# I2CRJ45X8-old.net
KiCad netlist of a schematic drawn in EAGLE
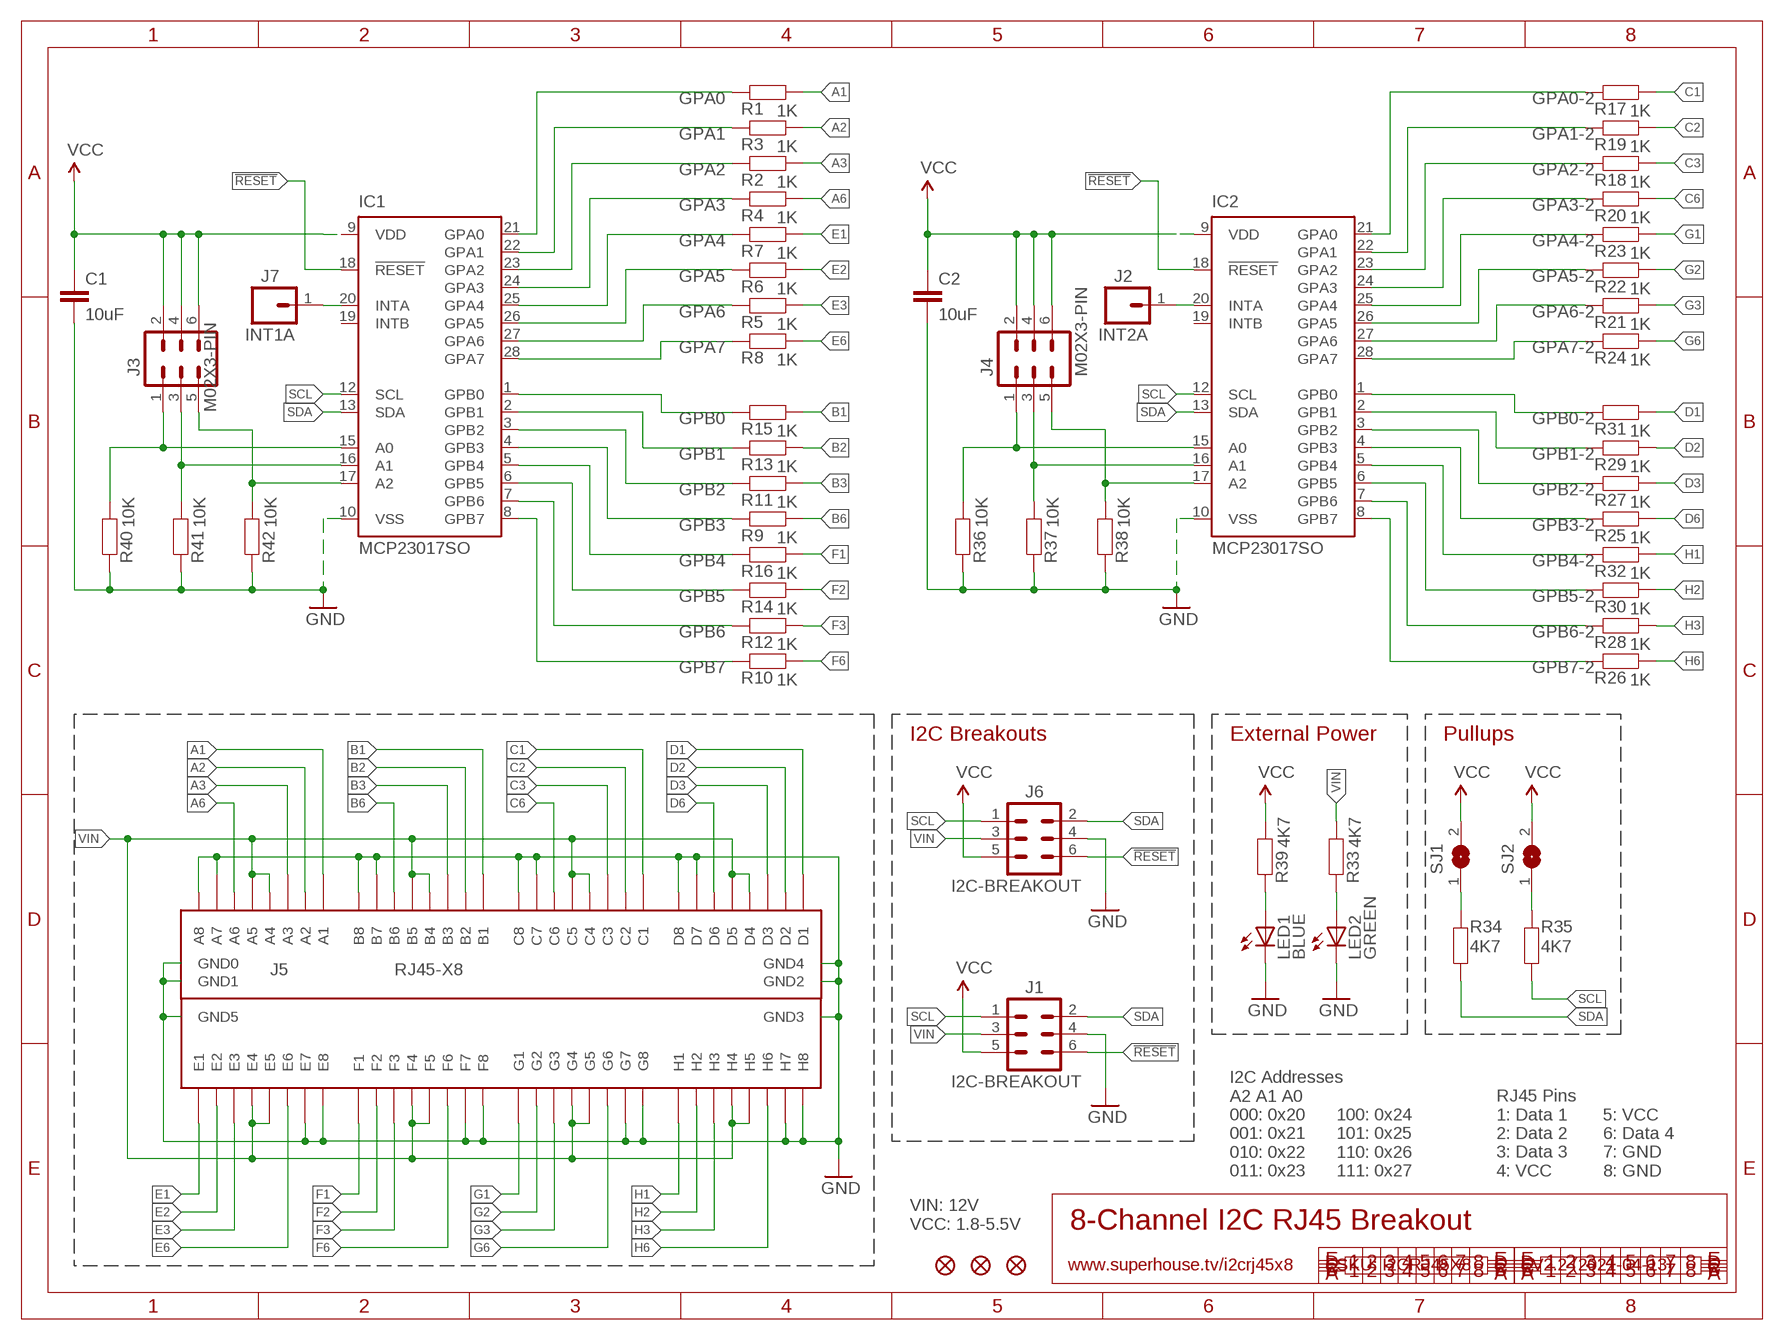
[diagram p0: schematic, sheet 1]

(export (version "E")
  (design (tool "Eeschema 10.0.6"))
  (components
    (comp (ref "C1")
      (value "10uF")
      (footprint "eagle-import:C0805")
      (libsource (lib "eagle-import") (part "CAP0805"))
    )
    (comp (ref "C2")
      (value "10uF")
      (footprint "eagle-import:C0805")
      (libsource (lib "eagle-import") (part "CAP0805"))
    )
    (comp (ref "FID1")
      (value "FIDUCIAL1X2.5")
      (footprint "eagle-import:FIDUCIAL-1X2.5")
      (libsource (lib "eagle-import") (part "FIDUCIAL1X2.5"))
    )
    (comp (ref "FID2")
      (value "FIDUCIAL1X2.5")
      (footprint "eagle-import:FIDUCIAL-1X2.5")
      (libsource (lib "eagle-import") (part "FIDUCIAL1X2.5"))
    )
    (comp (ref "FID3")
      (value "FIDUCIAL1X2.5")
      (footprint "eagle-import:FIDUCIAL-1X2.5")
      (libsource (lib "eagle-import") (part "FIDUCIAL1X2.5"))
    )
    (comp (ref "IC1")
      (value "MCP23017SO")
      (footprint "eagle-import:SO28W")
      (libsource (lib "eagle-import") (part "MCP23017SO"))
    )
    (comp (ref "IC2")
      (value "MCP23017SO")
      (footprint "eagle-import:SO28W")
      (libsource (lib "eagle-import") (part "MCP23017SO"))
    )
    (comp (ref "J1")
      (value "I2C-BREAKOUT")
      (footprint "eagle-import:2X03-SHROUDED")
      (libsource (lib "eagle-import") (part "M02X3-SHROUDED"))
    )
    (comp (ref "J2")
      (value "INT2A")
      (footprint "eagle-import:1X01")
      (libsource (lib "eagle-import") (part "M01-PLAIN"))
    )
    (comp (ref "J3")
      (value "M02X3-PIN")
      (footprint "eagle-import:2X03-P")
      (libsource (lib "eagle-import") (part "M02X3-PIN"))
    )
    (comp (ref "J4")
      (value "M02X3-PIN")
      (footprint "eagle-import:2X03-P")
      (libsource (lib "eagle-import") (part "M02X3-PIN"))
    )
    (comp (ref "J5")
      (value "RJ45-X8")
      (footprint "eagle-import:RJ45-2X4")
      (libsource (lib "eagle-import") (part "RJ45-X8"))
    )
    (comp (ref "J6")
      (value "I2C-BREAKOUT")
      (footprint "eagle-import:2X03-SHROUDED")
      (libsource (lib "eagle-import") (part "M02X3-SHROUDED"))
    )
    (comp (ref "J7")
      (value "INT1A")
      (footprint "eagle-import:1X01")
      (libsource (lib "eagle-import") (part "M01-PLAIN"))
    )
    (comp (ref "LED1")
      (value "BLUE")
      (footprint "eagle-import:LED-0603")
      (libsource (lib "eagle-import") (part "LED0603"))
    )
    (comp (ref "LED2")
      (value "GREEN")
      (footprint "eagle-import:LED-0603")
      (libsource (lib "eagle-import") (part "LED0603"))
    )
    (comp (ref "R1")
      (value "1K")
      (footprint "eagle-import:R0603")
      (libsource (lib "eagle-import") (part "RESISTOR0603"))
    )
    (comp (ref "R2")
      (value "1K")
      (footprint "eagle-import:R0603")
      (libsource (lib "eagle-import") (part "RESISTOR0603"))
    )
    (comp (ref "R3")
      (value "1K")
      (footprint "eagle-import:R0603")
      (libsource (lib "eagle-import") (part "RESISTOR0603"))
    )
    (comp (ref "R4")
      (value "1K")
      (footprint "eagle-import:R0603")
      (libsource (lib "eagle-import") (part "RESISTOR0603"))
    )
    (comp (ref "R5")
      (value "1K")
      (footprint "eagle-import:R0603")
      (libsource (lib "eagle-import") (part "RESISTOR0603"))
    )
    (comp (ref "R6")
      (value "1K")
      (footprint "eagle-import:R0603")
      (libsource (lib "eagle-import") (part "RESISTOR0603"))
    )
    (comp (ref "R7")
      (value "1K")
      (footprint "eagle-import:R0603")
      (libsource (lib "eagle-import") (part "RESISTOR0603"))
    )
    (comp (ref "R8")
      (value "1K")
      (footprint "eagle-import:R0603")
      (libsource (lib "eagle-import") (part "RESISTOR0603"))
    )
    (comp (ref "R9")
      (value "1K")
      (footprint "eagle-import:R0603")
      (libsource (lib "eagle-import") (part "RESISTOR0603"))
    )
    (comp (ref "R10")
      (value "1K")
      (footprint "eagle-import:R0603")
      (libsource (lib "eagle-import") (part "RESISTOR0603"))
    )
    (comp (ref "R11")
      (value "1K")
      (footprint "eagle-import:R0603")
      (libsource (lib "eagle-import") (part "RESISTOR0603"))
    )
    (comp (ref "R12")
      (value "1K")
      (footprint "eagle-import:R0603")
      (libsource (lib "eagle-import") (part "RESISTOR0603"))
    )
    (comp (ref "R13")
      (value "1K")
      (footprint "eagle-import:R0603")
      (libsource (lib "eagle-import") (part "RESISTOR0603"))
    )
    (comp (ref "R14")
      (value "1K")
      (footprint "eagle-import:R0603")
      (libsource (lib "eagle-import") (part "RESISTOR0603"))
    )
    (comp (ref "R15")
      (value "1K")
      (footprint "eagle-import:R0603")
      (libsource (lib "eagle-import") (part "RESISTOR0603"))
    )
    (comp (ref "R16")
      (value "1K")
      (footprint "eagle-import:R0603")
      (libsource (lib "eagle-import") (part "RESISTOR0603"))
    )
    (comp (ref "R17")
      (value "1K")
      (footprint "eagle-import:R0603")
      (libsource (lib "eagle-import") (part "RESISTOR0603"))
    )
    (comp (ref "R18")
      (value "1K")
      (footprint "eagle-import:R0603")
      (libsource (lib "eagle-import") (part "RESISTOR0603"))
    )
    (comp (ref "R19")
      (value "1K")
      (footprint "eagle-import:R0603")
      (libsource (lib "eagle-import") (part "RESISTOR0603"))
    )
    (comp (ref "R20")
      (value "1K")
      (footprint "eagle-import:R0603")
      (libsource (lib "eagle-import") (part "RESISTOR0603"))
    )
    (comp (ref "R21")
      (value "1K")
      (footprint "eagle-import:R0603")
      (libsource (lib "eagle-import") (part "RESISTOR0603"))
    )
    (comp (ref "R22")
      (value "1K")
      (footprint "eagle-import:R0603")
      (libsource (lib "eagle-import") (part "RESISTOR0603"))
    )
    (comp (ref "R23")
      (value "1K")
      (footprint "eagle-import:R0603")
      (libsource (lib "eagle-import") (part "RESISTOR0603"))
    )
    (comp (ref "R24")
      (value "1K")
      (footprint "eagle-import:R0603")
      (libsource (lib "eagle-import") (part "RESISTOR0603"))
    )
    (comp (ref "R25")
      (value "1K")
      (footprint "eagle-import:R0603")
      (libsource (lib "eagle-import") (part "RESISTOR0603"))
    )
    (comp (ref "R26")
      (value "1K")
      (footprint "eagle-import:R0603")
      (libsource (lib "eagle-import") (part "RESISTOR0603"))
    )
    (comp (ref "R27")
      (value "1K")
      (footprint "eagle-import:R0603")
      (libsource (lib "eagle-import") (part "RESISTOR0603"))
    )
    (comp (ref "R28")
      (value "1K")
      (footprint "eagle-import:R0603")
      (libsource (lib "eagle-import") (part "RESISTOR0603"))
    )
    (comp (ref "R29")
      (value "1K")
      (footprint "eagle-import:R0603")
      (libsource (lib "eagle-import") (part "RESISTOR0603"))
    )
    (comp (ref "R30")
      (value "1K")
      (footprint "eagle-import:R0603")
      (libsource (lib "eagle-import") (part "RESISTOR0603"))
    )
    (comp (ref "R31")
      (value "1K")
      (footprint "eagle-import:R0603")
      (libsource (lib "eagle-import") (part "RESISTOR0603"))
    )
    (comp (ref "R32")
      (value "1K")
      (footprint "eagle-import:R0603")
      (libsource (lib "eagle-import") (part "RESISTOR0603"))
    )
    (comp (ref "R33")
      (value "4K7")
      (footprint "eagle-import:R0603")
      (libsource (lib "eagle-import") (part "RESISTOR0603"))
    )
    (comp (ref "R34")
      (value "4K7")
      (footprint "eagle-import:R0603")
      (libsource (lib "eagle-import") (part "RESISTOR0603"))
    )
    (comp (ref "R35")
      (value "4K7")
      (footprint "eagle-import:R0603")
      (libsource (lib "eagle-import") (part "RESISTOR0603"))
    )
    (comp (ref "R36")
      (value "10K")
      (footprint "eagle-import:R0603")
      (libsource (lib "eagle-import") (part "RESISTOR0603"))
    )
    (comp (ref "R37")
      (value "10K")
      (footprint "eagle-import:R0603")
      (libsource (lib "eagle-import") (part "RESISTOR0603"))
    )
    (comp (ref "R38")
      (value "10K")
      (footprint "eagle-import:R0603")
      (libsource (lib "eagle-import") (part "RESISTOR0603"))
    )
    (comp (ref "R39")
      (value "4K7")
      (footprint "eagle-import:R0603")
      (libsource (lib "eagle-import") (part "RESISTOR0603"))
    )
    (comp (ref "R40")
      (value "10K")
      (footprint "eagle-import:R0603")
      (libsource (lib "eagle-import") (part "RESISTOR0603"))
    )
    (comp (ref "R41")
      (value "10K")
      (footprint "eagle-import:R0603")
      (libsource (lib "eagle-import") (part "RESISTOR0603"))
    )
    (comp (ref "R42")
      (value "10K")
      (footprint "eagle-import:R0603")
      (libsource (lib "eagle-import") (part "RESISTOR0603"))
    )
    (comp (ref "SJ1")
      (value "SJ-NORMAL")
      (footprint "eagle-import:SJ")
      (libsource (lib "eagle-import") (part "SJ-NORMAL"))
    )
    (comp (ref "SJ2")
      (value "SJ-NORMAL")
      (footprint "eagle-import:SJ")
      (libsource (lib "eagle-import") (part "SJ-NORMAL"))
    )
  )
  (nets
    (net (code "1") (name "/GPA0") (class "Default")
      (node (ref "IC1") (pin "21") (pinfunction "GPA0_21") (pintype "bidirectional"))
      (node (ref "R1") (pin "1") (pinfunction "1_1") (pintype "passive"))
    )
    (net (code "2") (name "/GPA0-2") (class "Default")
      (node (ref "IC2") (pin "21") (pinfunction "GPA0_21") (pintype "bidirectional"))
      (node (ref "R17") (pin "1") (pinfunction "1_1") (pintype "passive"))
    )
    (net (code "3") (name "/GPA1") (class "Default")
      (node (ref "IC1") (pin "22") (pinfunction "GPA1_22") (pintype "bidirectional"))
      (node (ref "R3") (pin "1") (pinfunction "1_1") (pintype "passive"))
    )
    (net (code "4") (name "/GPA1-2") (class "Default")
      (node (ref "IC2") (pin "22") (pinfunction "GPA1_22") (pintype "bidirectional"))
      (node (ref "R19") (pin "1") (pinfunction "1_1") (pintype "passive"))
    )
    (net (code "5") (name "/GPA2") (class "Default")
      (node (ref "IC1") (pin "23") (pinfunction "GPA2_23") (pintype "bidirectional"))
      (node (ref "R2") (pin "1") (pinfunction "1_1") (pintype "passive"))
    )
    (net (code "6") (name "/GPA2-2") (class "Default")
      (node (ref "IC2") (pin "23") (pinfunction "GPA2_23") (pintype "bidirectional"))
      (node (ref "R18") (pin "1") (pinfunction "1_1") (pintype "passive"))
    )
    (net (code "7") (name "/GPA3") (class "Default")
      (node (ref "IC1") (pin "24") (pinfunction "GPA3_24") (pintype "bidirectional"))
      (node (ref "R4") (pin "1") (pinfunction "1_1") (pintype "passive"))
    )
    (net (code "8") (name "/GPA3-2") (class "Default")
      (node (ref "IC2") (pin "24") (pinfunction "GPA3_24") (pintype "bidirectional"))
      (node (ref "R20") (pin "1") (pinfunction "1_1") (pintype "passive"))
    )
    (net (code "9") (name "/GPA4") (class "Default")
      (node (ref "IC1") (pin "25") (pinfunction "GPA4_25") (pintype "bidirectional"))
      (node (ref "R7") (pin "1") (pinfunction "1_1") (pintype "passive"))
    )
    (net (code "10") (name "/GPA4-2") (class "Default")
      (node (ref "IC2") (pin "25") (pinfunction "GPA4_25") (pintype "bidirectional"))
      (node (ref "R23") (pin "1") (pinfunction "1_1") (pintype "passive"))
    )
    (net (code "11") (name "/GPA5") (class "Default")
      (node (ref "IC1") (pin "26") (pinfunction "GPA5_26") (pintype "bidirectional"))
      (node (ref "R6") (pin "1") (pinfunction "1_1") (pintype "passive"))
    )
    (net (code "12") (name "/GPA5-2") (class "Default")
      (node (ref "IC2") (pin "26") (pinfunction "GPA5_26") (pintype "bidirectional"))
      (node (ref "R22") (pin "1") (pinfunction "1_1") (pintype "passive"))
    )
    (net (code "13") (name "/GPA6") (class "Default")
      (node (ref "IC1") (pin "27") (pinfunction "GPA6_27") (pintype "bidirectional"))
      (node (ref "R5") (pin "1") (pinfunction "1_1") (pintype "passive"))
    )
    (net (code "14") (name "/GPA6-2") (class "Default")
      (node (ref "IC2") (pin "27") (pinfunction "GPA6_27") (pintype "bidirectional"))
      (node (ref "R21") (pin "1") (pinfunction "1_1") (pintype "passive"))
    )
    (net (code "15") (name "/GPA7") (class "Default")
      (node (ref "IC1") (pin "28") (pinfunction "GPA7_28") (pintype "bidirectional"))
      (node (ref "R8") (pin "1") (pinfunction "1_1") (pintype "passive"))
    )
    (net (code "16") (name "/GPA7-2") (class "Default")
      (node (ref "IC2") (pin "28") (pinfunction "GPA7_28") (pintype "bidirectional"))
      (node (ref "R24") (pin "1") (pinfunction "1_1") (pintype "passive"))
    )
    (net (code "17") (name "/GPB0") (class "Default")
      (node (ref "IC1") (pin "1") (pinfunction "GPB0_1") (pintype "bidirectional"))
      (node (ref "R15") (pin "1") (pinfunction "1_1") (pintype "passive"))
    )
    (net (code "18") (name "/GPB0-2") (class "Default")
      (node (ref "IC2") (pin "1") (pinfunction "GPB0_1") (pintype "bidirectional"))
      (node (ref "R31") (pin "1") (pinfunction "1_1") (pintype "passive"))
    )
    (net (code "19") (name "/GPB1") (class "Default")
      (node (ref "IC1") (pin "2") (pinfunction "GPB1_2") (pintype "bidirectional"))
      (node (ref "R13") (pin "1") (pinfunction "1_1") (pintype "passive"))
    )
    (net (code "20") (name "/GPB1-2") (class "Default")
      (node (ref "IC2") (pin "2") (pinfunction "GPB1_2") (pintype "bidirectional"))
      (node (ref "R29") (pin "1") (pinfunction "1_1") (pintype "passive"))
    )
    (net (code "21") (name "/GPB2") (class "Default")
      (node (ref "IC1") (pin "3") (pinfunction "GPB2_3") (pintype "bidirectional"))
      (node (ref "R11") (pin "1") (pinfunction "1_1") (pintype "passive"))
    )
    (net (code "22") (name "/GPB2-2") (class "Default")
      (node (ref "IC2") (pin "3") (pinfunction "GPB2_3") (pintype "bidirectional"))
      (node (ref "R27") (pin "1") (pinfunction "1_1") (pintype "passive"))
    )
    (net (code "23") (name "/GPB3") (class "Default")
      (node (ref "IC1") (pin "4") (pinfunction "GPB3_4") (pintype "bidirectional"))
      (node (ref "R9") (pin "1") (pinfunction "1_1") (pintype "passive"))
    )
    (net (code "24") (name "/GPB3-2") (class "Default")
      (node (ref "IC2") (pin "4") (pinfunction "GPB3_4") (pintype "bidirectional"))
      (node (ref "R25") (pin "1") (pinfunction "1_1") (pintype "passive"))
    )
    (net (code "25") (name "/GPB4") (class "Default")
      (node (ref "IC1") (pin "5") (pinfunction "GPB4_5") (pintype "bidirectional"))
      (node (ref "R16") (pin "1") (pinfunction "1_1") (pintype "passive"))
    )
    (net (code "26") (name "/GPB4-2") (class "Default")
      (node (ref "IC2") (pin "5") (pinfunction "GPB4_5") (pintype "bidirectional"))
      (node (ref "R32") (pin "1") (pinfunction "1_1") (pintype "passive"))
    )
    (net (code "27") (name "/GPB5") (class "Default")
      (node (ref "IC1") (pin "6") (pinfunction "GPB5_6") (pintype "bidirectional"))
      (node (ref "R14") (pin "1") (pinfunction "1_1") (pintype "passive"))
    )
    (net (code "28") (name "/GPB5-2") (class "Default")
      (node (ref "IC2") (pin "6") (pinfunction "GPB5_6") (pintype "bidirectional"))
      (node (ref "R30") (pin "1") (pinfunction "1_1") (pintype "passive"))
    )
    (net (code "29") (name "/GPB6") (class "Default")
      (node (ref "IC1") (pin "7") (pinfunction "GPB6_7") (pintype "bidirectional"))
      (node (ref "R12") (pin "1") (pinfunction "1_1") (pintype "passive"))
    )
    (net (code "30") (name "/GPB6-2") (class "Default")
      (node (ref "IC2") (pin "7") (pinfunction "GPB6_7") (pintype "bidirectional"))
      (node (ref "R28") (pin "1") (pinfunction "1_1") (pintype "passive"))
    )
    (net (code "31") (name "/GPB7") (class "Default")
      (node (ref "IC1") (pin "8") (pinfunction "GPB7_8") (pintype "bidirectional"))
      (node (ref "R10") (pin "1") (pinfunction "1_1") (pintype "passive"))
    )
    (net (code "32") (name "/GPB7-2") (class "Default")
      (node (ref "IC2") (pin "8") (pinfunction "GPB7_8") (pintype "bidirectional"))
      (node (ref "R26") (pin "1") (pinfunction "1_1") (pintype "passive"))
    )
    (net (code "33") (name "/~{RESET}") (class "Default")
      (node (ref "IC1") (pin "18") (pinfunction "~{RESET}_18") (pintype "input"))
      (node (ref "IC2") (pin "18") (pinfunction "~{RESET}_18") (pintype "input"))
      (node (ref "J1") (pin "6") (pinfunction "6_6") (pintype "passive"))
      (node (ref "J6") (pin "6") (pinfunction "6_6") (pintype "passive"))
    )
    (net (code "34") (name "A1") (class "Default")
      (node (ref "J5") (pin "A1") (pinfunction "A1_A1") (pintype "bidirectional"))
      (node (ref "R1") (pin "2") (pinfunction "2_2") (pintype "passive"))
    )
    (net (code "35") (name "A2") (class "Default")
      (node (ref "J5") (pin "A2") (pinfunction "A2_A2") (pintype "bidirectional"))
      (node (ref "R3") (pin "2") (pinfunction "2_2") (pintype "passive"))
    )
    (net (code "36") (name "A3") (class "Default")
      (node (ref "J5") (pin "A3") (pinfunction "A3_A3") (pintype "bidirectional"))
      (node (ref "R2") (pin "2") (pinfunction "2_2") (pintype "passive"))
    )
    (net (code "37") (name "A6") (class "Default")
      (node (ref "J5") (pin "A6") (pinfunction "A6_A6") (pintype "bidirectional"))
      (node (ref "R4") (pin "2") (pinfunction "2_2") (pintype "passive"))
    )
    (net (code "38") (name "B1") (class "Default")
      (node (ref "J5") (pin "B1") (pinfunction "B1_B1") (pintype "bidirectional"))
      (node (ref "R15") (pin "2") (pinfunction "2_2") (pintype "passive"))
    )
    (net (code "39") (name "B2") (class "Default")
      (node (ref "J5") (pin "B2") (pinfunction "B2_B2") (pintype "bidirectional"))
      (node (ref "R13") (pin "2") (pinfunction "2_2") (pintype "passive"))
    )
    (net (code "40") (name "B3") (class "Default")
      (node (ref "J5") (pin "B3") (pinfunction "B3_B3") (pintype "bidirectional"))
      (node (ref "R11") (pin "2") (pinfunction "2_2") (pintype "passive"))
    )
    (net (code "41") (name "B6") (class "Default")
      (node (ref "J5") (pin "B6") (pinfunction "B6_B6") (pintype "bidirectional"))
      (node (ref "R9") (pin "2") (pinfunction "2_2") (pintype "passive"))
    )
    (net (code "42") (name "C1") (class "Default")
      (node (ref "J5") (pin "C1") (pinfunction "C1_C1") (pintype "bidirectional"))
      (node (ref "R17") (pin "2") (pinfunction "2_2") (pintype "passive"))
    )
    (net (code "43") (name "C2") (class "Default")
      (node (ref "J5") (pin "C2") (pinfunction "C2_C2") (pintype "bidirectional"))
      (node (ref "R19") (pin "2") (pinfunction "2_2") (pintype "passive"))
    )
    (net (code "44") (name "C3") (class "Default")
      (node (ref "J5") (pin "C3") (pinfunction "C3_C3") (pintype "bidirectional"))
      (node (ref "R18") (pin "2") (pinfunction "2_2") (pintype "passive"))
    )
    (net (code "45") (name "C6") (class "Default")
      (node (ref "J5") (pin "C6") (pinfunction "C6_C6") (pintype "bidirectional"))
      (node (ref "R20") (pin "2") (pinfunction "2_2") (pintype "passive"))
    )
    (net (code "46") (name "D1") (class "Default")
      (node (ref "J5") (pin "D1") (pinfunction "D1_D1") (pintype "bidirectional"))
      (node (ref "R31") (pin "2") (pinfunction "2_2") (pintype "passive"))
    )
    (net (code "47") (name "D2") (class "Default")
      (node (ref "J5") (pin "D2") (pinfunction "D2_D2") (pintype "bidirectional"))
      (node (ref "R29") (pin "2") (pinfunction "2_2") (pintype "passive"))
    )
    (net (code "48") (name "D3") (class "Default")
      (node (ref "J5") (pin "D3") (pinfunction "D3_D3") (pintype "bidirectional"))
      (node (ref "R27") (pin "2") (pinfunction "2_2") (pintype "passive"))
    )
    (net (code "49") (name "D6") (class "Default")
      (node (ref "J5") (pin "D6") (pinfunction "D6_D6") (pintype "bidirectional"))
      (node (ref "R25") (pin "2") (pinfunction "2_2") (pintype "passive"))
    )
    (net (code "50") (name "E1") (class "Default")
      (node (ref "J5") (pin "E1") (pinfunction "E1_E1") (pintype "bidirectional"))
      (node (ref "R7") (pin "2") (pinfunction "2_2") (pintype "passive"))
    )
    (net (code "51") (name "E2") (class "Default")
      (node (ref "J5") (pin "E2") (pinfunction "E2_E2") (pintype "bidirectional"))
      (node (ref "R6") (pin "2") (pinfunction "2_2") (pintype "passive"))
    )
    (net (code "52") (name "E3") (class "Default")
      (node (ref "J5") (pin "E3") (pinfunction "E3_E3") (pintype "bidirectional"))
      (node (ref "R5") (pin "2") (pinfunction "2_2") (pintype "passive"))
    )
    (net (code "53") (name "E6") (class "Default")
      (node (ref "J5") (pin "E6") (pinfunction "E6_E6") (pintype "bidirectional"))
      (node (ref "R8") (pin "2") (pinfunction "2_2") (pintype "passive"))
    )
    (net (code "54") (name "F1") (class "Default")
      (node (ref "J5") (pin "F1") (pinfunction "F1_F1") (pintype "bidirectional"))
      (node (ref "R16") (pin "2") (pinfunction "2_2") (pintype "passive"))
    )
    (net (code "55") (name "F2") (class "Default")
      (node (ref "J5") (pin "F2") (pinfunction "F2_F2") (pintype "bidirectional"))
      (node (ref "R14") (pin "2") (pinfunction "2_2") (pintype "passive"))
    )
    (net (code "56") (name "F3") (class "Default")
      (node (ref "J5") (pin "F3") (pinfunction "F3_F3") (pintype "bidirectional"))
      (node (ref "R12") (pin "2") (pinfunction "2_2") (pintype "passive"))
    )
    (net (code "57") (name "F6") (class "Default")
      (node (ref "J5") (pin "F6") (pinfunction "F6_F6") (pintype "bidirectional"))
      (node (ref "R10") (pin "2") (pinfunction "2_2") (pintype "passive"))
    )
    (net (code "58") (name "G1") (class "Default")
      (node (ref "J5") (pin "G1") (pinfunction "G1_G1") (pintype "bidirectional"))
      (node (ref "R23") (pin "2") (pinfunction "2_2") (pintype "passive"))
    )
    (net (code "59") (name "G2") (class "Default")
      (node (ref "J5") (pin "G2") (pinfunction "G2_G2") (pintype "bidirectional"))
      (node (ref "R22") (pin "2") (pinfunction "2_2") (pintype "passive"))
    )
    (net (code "60") (name "G3") (class "Default")
      (node (ref "J5") (pin "G3") (pinfunction "G3_G3") (pintype "bidirectional"))
      (node (ref "R21") (pin "2") (pinfunction "2_2") (pintype "passive"))
    )
    (net (code "61") (name "G6") (class "Default")
      (node (ref "J5") (pin "G6") (pinfunction "G6_G6") (pintype "bidirectional"))
      (node (ref "R24") (pin "2") (pinfunction "2_2") (pintype "passive"))
    )
    (net (code "62") (name "GND") (class "Default")
      (node (ref "C1") (pin "2") (pinfunction "2_2") (pintype "passive"))
      (node (ref "C2") (pin "2") (pinfunction "2_2") (pintype "passive"))
      (node (ref "IC1") (pin "10") (pinfunction "VSS_10") (pintype "power_in"))
      (node (ref "IC2") (pin "10") (pinfunction "VSS_10") (pintype "power_in"))
      (node (ref "J1") (pin "4") (pinfunction "4_4") (pintype "passive"))
      (node (ref "J5") (pin "A7") (pinfunction "A7_A7") (pintype "bidirectional"))
      (node (ref "J5") (pin "A8") (pinfunction "A8_A8") (pintype "bidirectional"))
      (node (ref "J5") (pin "B7") (pinfunction "B7_B7") (pintype "bidirectional"))
      (node (ref "J5") (pin "B8") (pinfunction "B8_B8") (pintype "bidirectional"))
      (node (ref "J5") (pin "C7") (pinfunction "C7_C7") (pintype "bidirectional"))
      (node (ref "J5") (pin "C8") (pinfunction "C8_C8") (pintype "bidirectional"))
      (node (ref "J5") (pin "D7") (pinfunction "D7_D7") (pintype "bidirectional"))
      (node (ref "J5") (pin "D8") (pinfunction "D8_D8") (pintype "bidirectional"))
      (node (ref "J5") (pin "E7") (pinfunction "E7_E7") (pintype "bidirectional"))
      (node (ref "J5") (pin "E8") (pinfunction "E8_E8") (pintype "bidirectional"))
      (node (ref "J5") (pin "F7") (pinfunction "F7_F7") (pintype "bidirectional"))
      (node (ref "J5") (pin "F8") (pinfunction "F8_F8") (pintype "bidirectional"))
      (node (ref "J5") (pin "G7") (pinfunction "G7_G7") (pintype "bidirectional"))
      (node (ref "J5") (pin "G8") (pinfunction "G8_G8") (pintype "bidirectional"))
      (node (ref "J5") (pin "GND0") (pinfunction "GND0_GND0") (pintype "power_in"))
      (node (ref "J5") (pin "GND1") (pinfunction "GND1_GND1") (pintype "power_in"))
      (node (ref "J5") (pin "GND2") (pinfunction "GND2_GND2") (pintype "power_in"))
      (node (ref "J5") (pin "GND3") (pinfunction "GND3_GND3") (pintype "power_in"))
      (node (ref "J5") (pin "GND4") (pinfunction "GND4_GND4") (pintype "power_in"))
      (node (ref "J5") (pin "GND5") (pinfunction "GND5_GND5") (pintype "power_in"))
      (node (ref "J5") (pin "H7") (pinfunction "H7_H7") (pintype "bidirectional"))
      (node (ref "J5") (pin "H8") (pinfunction "H8_H8") (pintype "bidirectional"))
      (node (ref "J6") (pin "4") (pinfunction "4_4") (pintype "passive"))
      (node (ref "LED1") (pin "C") (pinfunction "C_C") (pintype "passive"))
      (node (ref "LED2") (pin "C") (pinfunction "C_C") (pintype "passive"))
      (node (ref "R36") (pin "1") (pinfunction "1_1") (pintype "passive"))
      (node (ref "R37") (pin "1") (pinfunction "1_1") (pintype "passive"))
      (node (ref "R38") (pin "1") (pinfunction "1_1") (pintype "passive"))
      (node (ref "R40") (pin "1") (pinfunction "1_1") (pintype "passive"))
      (node (ref "R41") (pin "1") (pinfunction "1_1") (pintype "passive"))
      (node (ref "R42") (pin "1") (pinfunction "1_1") (pintype "passive"))
    )
    (net (code "63") (name "H1") (class "Default")
      (node (ref "J5") (pin "H1") (pinfunction "H1_H1") (pintype "bidirectional"))
      (node (ref "R32") (pin "2") (pinfunction "2_2") (pintype "passive"))
    )
    (net (code "64") (name "H2") (class "Default")
      (node (ref "J5") (pin "H2") (pinfunction "H2_H2") (pintype "bidirectional"))
      (node (ref "R30") (pin "2") (pinfunction "2_2") (pintype "passive"))
    )
    (net (code "65") (name "H3") (class "Default")
      (node (ref "J5") (pin "H3") (pinfunction "H3_H3") (pintype "bidirectional"))
      (node (ref "R28") (pin "2") (pinfunction "2_2") (pintype "passive"))
    )
    (net (code "66") (name "H6") (class "Default")
      (node (ref "J5") (pin "H6") (pinfunction "H6_H6") (pintype "bidirectional"))
      (node (ref "R26") (pin "2") (pinfunction "2_2") (pintype "passive"))
    )
    (net (code "67") (name "Net-(IC1-A0)") (class "Default")
      (node (ref "IC1") (pin "15") (pinfunction "A0_15") (pintype "input"))
      (node (ref "J3") (pin "1") (pinfunction "1_1") (pintype "passive"))
      (node (ref "R40") (pin "2") (pinfunction "2_2") (pintype "passive"))
    )
    (net (code "68") (name "Net-(IC1-A1)") (class "Default")
      (node (ref "IC1") (pin "16") (pinfunction "A1_16") (pintype "input"))
      (node (ref "J3") (pin "3") (pinfunction "3_3") (pintype "passive"))
      (node (ref "R41") (pin "2") (pinfunction "2_2") (pintype "passive"))
    )
    (net (code "69") (name "Net-(IC1-A2)") (class "Default")
      (node (ref "IC1") (pin "17") (pinfunction "A2_17") (pintype "input"))
      (node (ref "J3") (pin "5") (pinfunction "5_5") (pintype "passive"))
      (node (ref "R42") (pin "2") (pinfunction "2_2") (pintype "passive"))
    )
    (net (code "70") (name "Net-(IC1-INTA)") (class "Default")
      (node (ref "IC1") (pin "20") (pinfunction "INTA_20") (pintype "output"))
      (node (ref "J7") (pin "1") (pinfunction "1_1") (pintype "passive"))
    )
    (net (code "71") (name "Net-(IC2-A0)") (class "Default")
      (node (ref "IC2") (pin "15") (pinfunction "A0_15") (pintype "input"))
      (node (ref "J4") (pin "1") (pinfunction "1_1") (pintype "passive"))
      (node (ref "R36") (pin "2") (pinfunction "2_2") (pintype "passive"))
    )
    (net (code "72") (name "Net-(IC2-A1)") (class "Default")
      (node (ref "IC2") (pin "16") (pinfunction "A1_16") (pintype "input"))
      (node (ref "J4") (pin "3") (pinfunction "3_3") (pintype "passive"))
      (node (ref "R37") (pin "2") (pinfunction "2_2") (pintype "passive"))
    )
    (net (code "73") (name "Net-(IC2-A2)") (class "Default")
      (node (ref "IC2") (pin "17") (pinfunction "A2_17") (pintype "input"))
      (node (ref "J4") (pin "5") (pinfunction "5_5") (pintype "passive"))
      (node (ref "R38") (pin "2") (pinfunction "2_2") (pintype "passive"))
    )
    (net (code "74") (name "Net-(IC2-INTA)") (class "Default")
      (node (ref "IC2") (pin "20") (pinfunction "INTA_20") (pintype "output"))
      (node (ref "J2") (pin "1") (pinfunction "1_1") (pintype "passive"))
    )
    (net (code "75") (name "Net-(LED1-PadA)") (class "Default")
      (node (ref "LED1") (pin "A") (pinfunction "A_A") (pintype "passive"))
      (node (ref "R39") (pin "1") (pinfunction "1_1") (pintype "passive"))
    )
    (net (code "76") (name "Net-(LED2-PadA)") (class "Default")
      (node (ref "LED2") (pin "A") (pinfunction "A_A") (pintype "passive"))
      (node (ref "R33") (pin "1") (pinfunction "1_1") (pintype "passive"))
    )
    (net (code "77") (name "Net-(R34-Pad2)") (class "Default")
      (node (ref "R34") (pin "2") (pinfunction "2_2") (pintype "passive"))
      (node (ref "SJ1") (pin "1") (pinfunction "1_1") (pintype "passive"))
    )
    (net (code "78") (name "Net-(R35-Pad2)") (class "Default")
      (node (ref "R35") (pin "2") (pinfunction "2_2") (pintype "passive"))
      (node (ref "SJ2") (pin "1") (pinfunction "1_1") (pintype "passive"))
    )
    (net (code "79") (name "SCL") (class "Default")
      (node (ref "IC1") (pin "12") (pinfunction "SCL_12") (pintype "input"))
      (node (ref "IC2") (pin "12") (pinfunction "SCL_12") (pintype "input"))
      (node (ref "J1") (pin "1") (pinfunction "1_1") (pintype "passive"))
      (node (ref "J6") (pin "1") (pinfunction "1_1") (pintype "passive"))
      (node (ref "R35") (pin "1") (pinfunction "1_1") (pintype "passive"))
    )
    (net (code "80") (name "SDA") (class "Default")
      (node (ref "IC1") (pin "13") (pinfunction "SDA_13") (pintype "bidirectional"))
      (node (ref "IC2") (pin "13") (pinfunction "SDA_13") (pintype "bidirectional"))
      (node (ref "J1") (pin "2") (pinfunction "2_2") (pintype "passive"))
      (node (ref "J6") (pin "2") (pinfunction "2_2") (pintype "passive"))
      (node (ref "R34") (pin "1") (pinfunction "1_1") (pintype "passive"))
    )
    (net (code "81") (name "VCC") (class "Default")
      (node (ref "C1") (pin "1") (pinfunction "1_1") (pintype "passive"))
      (node (ref "C2") (pin "1") (pinfunction "1_1") (pintype "passive"))
      (node (ref "IC1") (pin "9") (pinfunction "VDD_9") (pintype "power_in"))
      (node (ref "IC2") (pin "9") (pinfunction "VDD_9") (pintype "power_in"))
      (node (ref "J1") (pin "5") (pinfunction "5_5") (pintype "passive"))
      (node (ref "J3") (pin "2") (pinfunction "2_2") (pintype "passive"))
      (node (ref "J3") (pin "4") (pinfunction "4_4") (pintype "passive"))
      (node (ref "J3") (pin "6") (pinfunction "6_6") (pintype "passive"))
      (node (ref "J4") (pin "2") (pinfunction "2_2") (pintype "passive"))
      (node (ref "J4") (pin "4") (pinfunction "4_4") (pintype "passive"))
      (node (ref "J4") (pin "6") (pinfunction "6_6") (pintype "passive"))
      (node (ref "J6") (pin "5") (pinfunction "5_5") (pintype "passive"))
      (node (ref "R39") (pin "2") (pinfunction "2_2") (pintype "passive"))
      (node (ref "SJ1") (pin "2") (pinfunction "2_2") (pintype "passive"))
      (node (ref "SJ2") (pin "2") (pinfunction "2_2") (pintype "passive"))
    )
    (net (code "82") (name "VIN") (class "Default")
      (node (ref "J1") (pin "3") (pinfunction "3_3") (pintype "passive"))
      (node (ref "J5") (pin "A4") (pinfunction "A4_A4") (pintype "bidirectional"))
      (node (ref "J5") (pin "A5") (pinfunction "A5_A5") (pintype "bidirectional"))
      (node (ref "J5") (pin "B4") (pinfunction "B4_B4") (pintype "bidirectional"))
      (node (ref "J5") (pin "B5") (pinfunction "B5_B5") (pintype "bidirectional"))
      (node (ref "J5") (pin "C4") (pinfunction "C4_C4") (pintype "bidirectional"))
      (node (ref "J5") (pin "C5") (pinfunction "C5_C5") (pintype "bidirectional"))
      (node (ref "J5") (pin "D4") (pinfunction "D4_D4") (pintype "bidirectional"))
      (node (ref "J5") (pin "D5") (pinfunction "D5_D5") (pintype "bidirectional"))
      (node (ref "J5") (pin "E4") (pinfunction "E4_E4") (pintype "bidirectional"))
      (node (ref "J5") (pin "E5") (pinfunction "E5_E5") (pintype "bidirectional"))
      (node (ref "J5") (pin "F4") (pinfunction "F4_F4") (pintype "bidirectional"))
      (node (ref "J5") (pin "F5") (pinfunction "F5_F5") (pintype "bidirectional"))
      (node (ref "J5") (pin "G4") (pinfunction "G4_G4") (pintype "bidirectional"))
      (node (ref "J5") (pin "G5") (pinfunction "G5_G5") (pintype "bidirectional"))
      (node (ref "J5") (pin "H4") (pinfunction "H4_H4") (pintype "bidirectional"))
      (node (ref "J5") (pin "H5") (pinfunction "H5_H5") (pintype "bidirectional"))
      (node (ref "J6") (pin "3") (pinfunction "3_3") (pintype "passive"))
      (node (ref "R33") (pin "2") (pinfunction "2_2") (pintype "passive"))
    )
    (net (code "83") (name "unconnected-(IC1-INTB-Pad19)") (class "Default")
      (node (ref "IC1") (pin "19") (pinfunction "INTB_19") (pintype "output"))
    )
    (net (code "84") (name "unconnected-(IC2-INTB-Pad19)") (class "Default")
      (node (ref "IC2") (pin "19") (pinfunction "INTB_19") (pintype "output"))
    )
  )
)
